# amp_soha.net
KiCad netlist of a schematic drawn in EAGLE
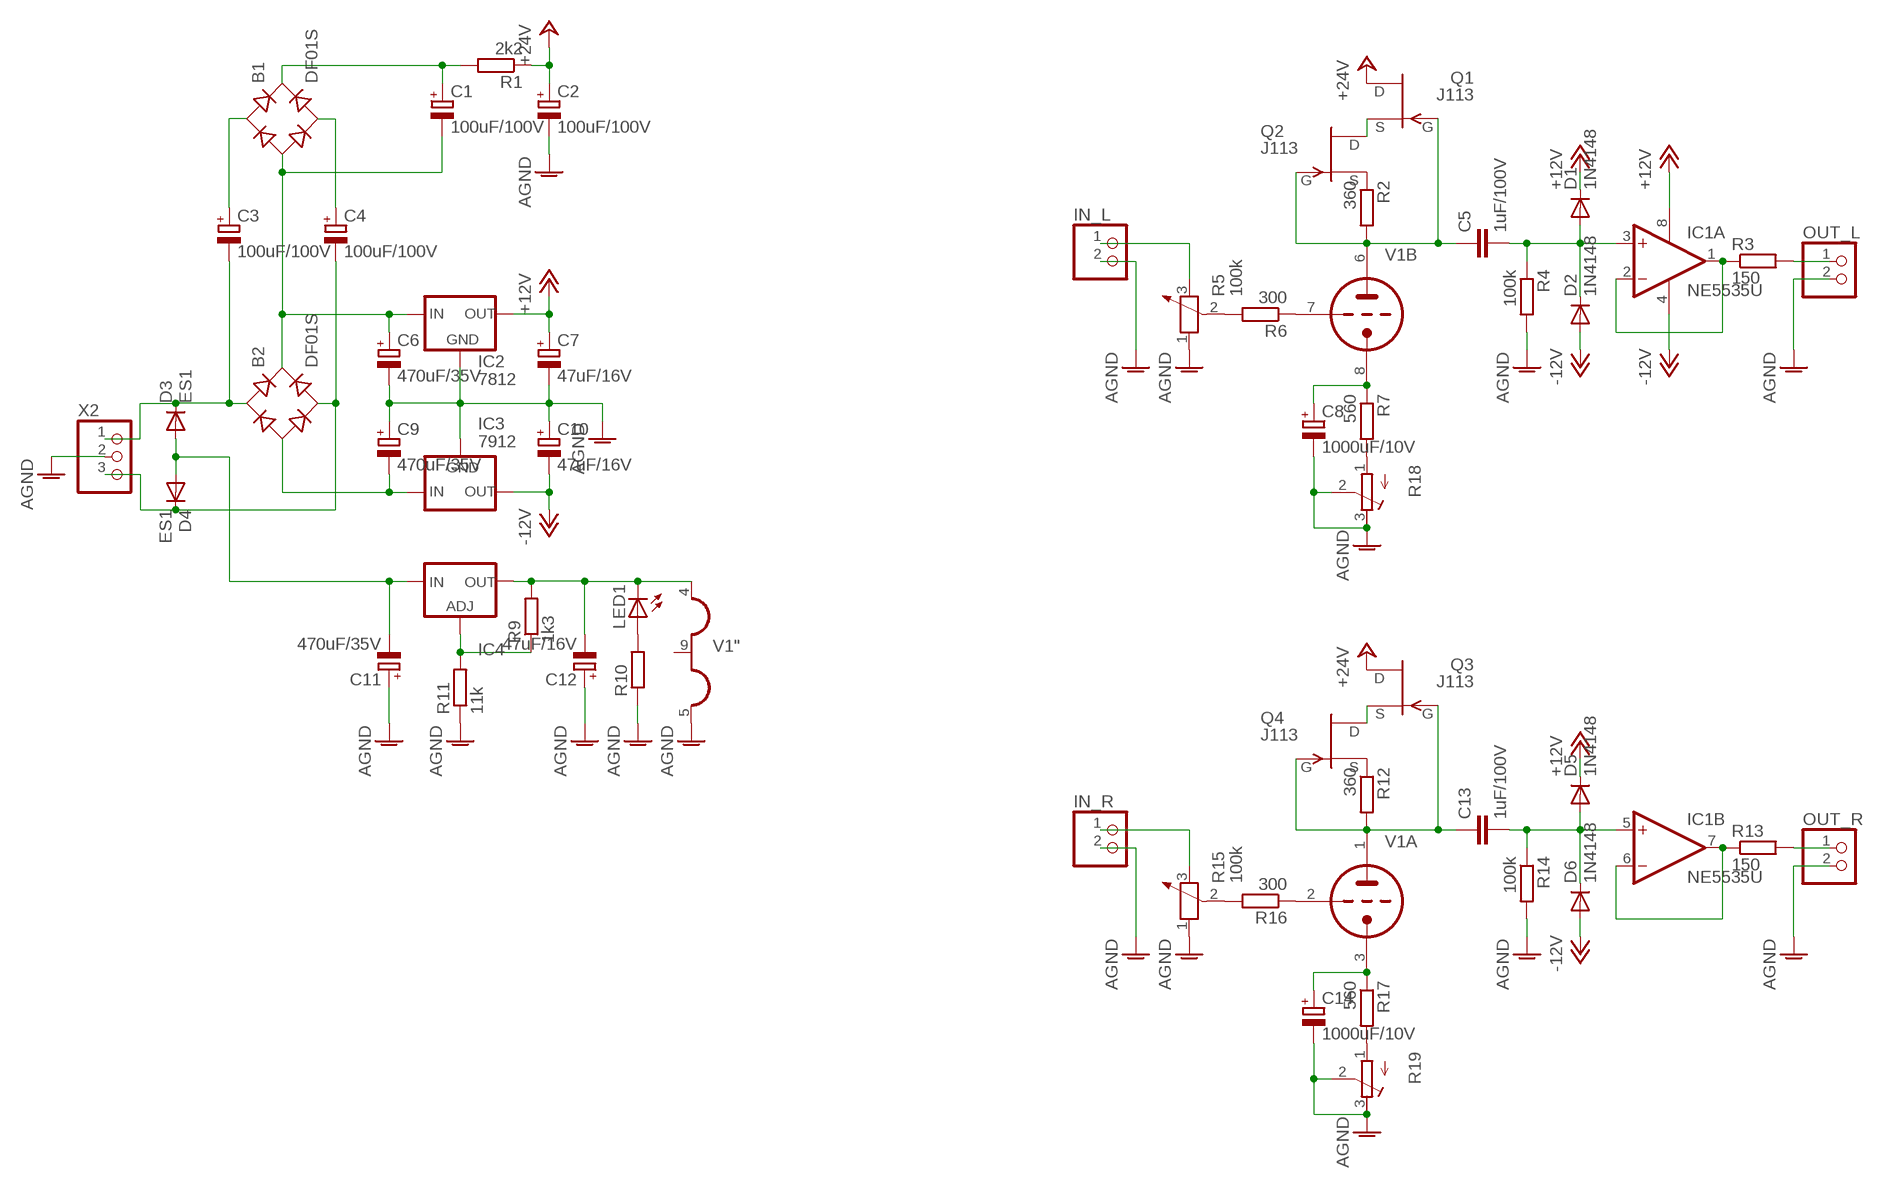
[diagram p0: schematic, sheet 1]

(export (version "E")
  (design (tool "Eeschema 10.0.6"))
  (components
    (comp (ref "B1")
      (value "DF01S")
      (footprint "eagle-import:DFS")
      (libsource (lib "eagle-import") (part "DFS01"))
    )
    (comp (ref "B2")
      (value "DF01S")
      (footprint "eagle-import:DFS")
      (libsource (lib "eagle-import") (part "DFS01"))
    )
    (comp (ref "C1")
      (value "100uF/100V")
      (footprint "eagle-import:E5-10,5")
      (libsource (lib "eagle-import") (part "CPOL-EUE5-10,5"))
    )
    (comp (ref "C2")
      (value "100uF/100V")
      (footprint "eagle-import:E5-10,5")
      (libsource (lib "eagle-import") (part "CPOL-EUE5-10,5"))
    )
    (comp (ref "C3")
      (value "100uF/100V")
      (footprint "eagle-import:E5-10,5")
      (libsource (lib "eagle-import") (part "CPOL-EUE5-10,5"))
    )
    (comp (ref "C4")
      (value "100uF/100V")
      (footprint "eagle-import:E5-10,5")
      (libsource (lib "eagle-import") (part "CPOL-EUE5-10,5"))
    )
    (comp (ref "C5")
      (value "1uF/100V")
      (footprint "eagle-import:C075-052X106")
      (libsource (lib "eagle-import") (part "C-EU075-052X106"))
    )
    (comp (ref "C6")
      (value "470uF/35V")
      (footprint "eagle-import:E5-10,5")
      (libsource (lib "eagle-import") (part "CPOL-EUE5-10,5"))
    )
    (comp (ref "C7")
      (value "47uF/16V")
      (footprint "eagle-import:E2,5-6")
      (libsource (lib "eagle-import") (part "CPOL-EUE2.5-6"))
    )
    (comp (ref "C8")
      (value "1000uF/10V")
      (footprint "eagle-import:E5-10,5")
      (libsource (lib "eagle-import") (part "CPOL-EUE5-10,5"))
    )
    (comp (ref "C9")
      (value "470uF/35V")
      (footprint "eagle-import:E5-10,5")
      (libsource (lib "eagle-import") (part "CPOL-EUE5-10,5"))
    )
    (comp (ref "C10")
      (value "47uF/16V")
      (footprint "eagle-import:E2,5-6")
      (libsource (lib "eagle-import") (part "CPOL-EUE2.5-6"))
    )
    (comp (ref "C11")
      (value "470uF/35V")
      (footprint "eagle-import:E5-10,5")
      (libsource (lib "eagle-import") (part "CPOL-EUE5-10,5"))
    )
    (comp (ref "C12")
      (value "47uF/16V")
      (footprint "eagle-import:E2,5-6")
      (libsource (lib "eagle-import") (part "CPOL-EUE2.5-6"))
    )
    (comp (ref "C13")
      (value "1uF/100V")
      (footprint "eagle-import:C075-052X106")
      (libsource (lib "eagle-import") (part "C-EU075-052X106"))
    )
    (comp (ref "C14")
      (value "1000uF/10V")
      (footprint "eagle-import:E5-10,5")
      (libsource (lib "eagle-import") (part "CPOL-EUE5-10,5"))
    )
    (comp (ref "D1")
      (value "1N4148")
      (footprint "eagle-import:D0805")
      (libsource (lib "eagle-import") (part "1N4148"))
    )
    (comp (ref "D2")
      (value "1N4148")
      (footprint "eagle-import:D0805")
      (libsource (lib "eagle-import") (part "1N4148"))
    )
    (comp (ref "D3")
      (value "ES1")
      (footprint "eagle-import:DO-214AC")
      (libsource (lib "eagle-import") (part "ES1"))
    )
    (comp (ref "D4")
      (value "ES1")
      (footprint "eagle-import:DO-214AC")
      (libsource (lib "eagle-import") (part "ES1"))
    )
    (comp (ref "D5")
      (value "1N4148")
      (footprint "eagle-import:D0805")
      (libsource (lib "eagle-import") (part "1N4148"))
    )
    (comp (ref "D6")
      (value "1N4148")
      (footprint "eagle-import:D0805")
      (libsource (lib "eagle-import") (part "1N4148"))
    )
    (comp (ref "IC1")
      (value "NE5535U")
      (footprint "eagle-import:SO08")
      (libsource (lib "eagle-import") (part "NE5535U"))
    )
    (comp (ref "IC2")
      (value "7812")
      (footprint "eagle-import:78XXS")
      (libsource (lib "eagle-import") (part "78XXTO-220"))
    )
    (comp (ref "IC3")
      (value "7912")
      (footprint "eagle-import:79XXS")
      (libsource (lib "eagle-import") (part "79XXTO-220"))
    )
    (comp (ref "IC4")
      (value "LM337TS")
      (footprint "eagle-import:337TS")
      (libsource (lib "eagle-import") (part "LM337TS"))
    )
    (comp (ref "IN_L")
      (value "PINHD-1X2")
      (footprint "eagle-import:1X02")
      (libsource (lib "eagle-import") (part "PINHD-1X2"))
    )
    (comp (ref "IN_R")
      (value "PINHD-1X2")
      (footprint "eagle-import:1X02")
      (libsource (lib "eagle-import") (part "PINHD-1X2"))
    )
    (comp (ref "LED1")
      (value "LED5MM")
      (footprint "eagle-import:LED5MM")
      (libsource (lib "eagle-import") (part "LED5MM"))
    )
    (comp (ref "OUT_L")
      (value "PINHD-1X2")
      (footprint "eagle-import:1X02")
      (libsource (lib "eagle-import") (part "PINHD-1X2"))
    )
    (comp (ref "OUT_R")
      (value "PINHD-1X2")
      (footprint "eagle-import:1X02")
      (libsource (lib "eagle-import") (part "PINHD-1X2"))
    )
    (comp (ref "Q1")
      (value "J113")
      (footprint "eagle-import:TO92")
      (libsource (lib "eagle-import") (part "J113"))
    )
    (comp (ref "Q2")
      (value "J113")
      (footprint "eagle-import:TO92")
      (libsource (lib "eagle-import") (part "J113"))
    )
    (comp (ref "Q3")
      (value "J113")
      (footprint "eagle-import:TO92")
      (libsource (lib "eagle-import") (part "J113"))
    )
    (comp (ref "Q4")
      (value "J113")
      (footprint "eagle-import:TO92")
      (libsource (lib "eagle-import") (part "J113"))
    )
    (comp (ref "R1")
      (value "2k2")
      (footprint "eagle-import:R0805")
      (libsource (lib "eagle-import") (part "R-EU_"))
    )
    (comp (ref "R2")
      (value "360")
      (footprint "eagle-import:R0805")
      (libsource (lib "eagle-import") (part "R-EU_"))
    )
    (comp (ref "R3")
      (value "150")
      (footprint "eagle-import:R0805")
      (libsource (lib "eagle-import") (part "R-EU_"))
    )
    (comp (ref "R4")
      (value "100k")
      (footprint "eagle-import:R0805")
      (libsource (lib "eagle-import") (part "R-EU_"))
    )
    (comp (ref "R5")
      (value "100k")
      (footprint "eagle-import:1X03")
      (libsource (lib "eagle-import") (part "POTENTIOMETER_"))
    )
    (comp (ref "R6")
      (value "300")
      (footprint "eagle-import:R0805")
      (libsource (lib "eagle-import") (part "R-EU_"))
    )
    (comp (ref "R7")
      (value "560")
      (footprint "eagle-import:R0805")
      (libsource (lib "eagle-import") (part "R-EU_"))
    )
    (comp (ref "R9")
      (value "1k3")
      (footprint "eagle-import:R0805")
      (libsource (lib "eagle-import") (part "R-EU_"))
    )
    (comp (ref "R10")
      (value "R-EU_")
      (footprint "eagle-import:R0805")
      (libsource (lib "eagle-import") (part "R-EU_"))
    )
    (comp (ref "R11")
      (value "11k")
      (footprint "eagle-import:R0805")
      (libsource (lib "eagle-import") (part "R-EU_"))
    )
    (comp (ref "R12")
      (value "360")
      (footprint "eagle-import:R0805")
      (libsource (lib "eagle-import") (part "R-EU_"))
    )
    (comp (ref "R13")
      (value "150")
      (footprint "eagle-import:R0805")
      (libsource (lib "eagle-import") (part "R-EU_"))
    )
    (comp (ref "R14")
      (value "100k")
      (footprint "eagle-import:R0805")
      (libsource (lib "eagle-import") (part "R-EU_"))
    )
    (comp (ref "R15")
      (value "100k")
      (footprint "eagle-import:1X03")
      (libsource (lib "eagle-import") (part "POTENTIOMETER_"))
    )
    (comp (ref "R16")
      (value "300")
      (footprint "eagle-import:R0805")
      (libsource (lib "eagle-import") (part "R-EU_"))
    )
    (comp (ref "R17")
      (value "560")
      (footprint "eagle-import:R0805")
      (libsource (lib "eagle-import") (part "R-EU_"))
    )
    (comp (ref "R18")
      (value "RTRIM329Y")
      (footprint "eagle-import:RTRIM3296Y")
      (libsource (lib "eagle-import") (part "RTRIM329Y"))
    )
    (comp (ref "R19")
      (value "RTRIM329Y")
      (footprint "eagle-import:RTRIM3296Y")
      (libsource (lib "eagle-import") (part "RTRIM329Y"))
    )
    (comp (ref "V1")
      (value "12AU7-P")
      (footprint "eagle-import:NOVAL")
      (libsource (lib "eagle-import") (part "12AU7-P"))
    )
    (comp (ref "X2")
      (value "W237-103")
      (footprint "eagle-import:W237-103")
      (libsource (lib "eagle-import") (part "W237-103"))
    )
  )
  (nets
    (net (code "1") (name "+12V") (class "Default")
      (node (ref "C7") (pin "+") (pinfunction "+_+") (pintype "passive"))
      (node (ref "D1") (pin "K") (pinfunction "C_K") (pintype "passive"))
      (node (ref "D5") (pin "K") (pinfunction "C_K") (pintype "passive"))
      (node (ref "IC1") (pin "8") (pinfunction "V+_8") (pintype "power_in"))
      (node (ref "IC2") (pin "OUT") (pinfunction "OUT_OUT") (pintype "passive"))
    )
    (net (code "2") (name "+24V") (class "Default")
      (node (ref "C2") (pin "+") (pinfunction "+_+") (pintype "passive"))
      (node (ref "Q1") (pin "3") (pinfunction "D_3") (pintype "passive"))
      (node (ref "Q3") (pin "3") (pinfunction "D_3") (pintype "passive"))
      (node (ref "R1") (pin "1") (pinfunction "1_1") (pintype "passive"))
    )
    (net (code "3") (name "-12V") (class "Default")
      (node (ref "C10") (pin "-") (pinfunction "-_-") (pintype "passive"))
      (node (ref "D2") (pin "A") (pinfunction "A_A") (pintype "passive"))
      (node (ref "D6") (pin "A") (pinfunction "A_A") (pintype "passive"))
      (node (ref "IC1") (pin "4") (pinfunction "V-_4") (pintype "power_in"))
      (node (ref "IC3") (pin "OUT") (pinfunction "OUT_OUT") (pintype "passive"))
    )
    (net (code "4") (name "AGND") (class "Default")
      (node (ref "C10") (pin "+") (pinfunction "+_+") (pintype "passive"))
      (node (ref "C11") (pin "+") (pinfunction "+_+") (pintype "passive"))
      (node (ref "C12") (pin "+") (pinfunction "+_+") (pintype "passive"))
      (node (ref "C14") (pin "-") (pinfunction "-_-") (pintype "passive"))
      (node (ref "C2") (pin "-") (pinfunction "-_-") (pintype "passive"))
      (node (ref "C6") (pin "-") (pinfunction "-_-") (pintype "passive"))
      (node (ref "C7") (pin "-") (pinfunction "-_-") (pintype "passive"))
      (node (ref "C8") (pin "-") (pinfunction "-_-") (pintype "passive"))
      (node (ref "C9") (pin "+") (pinfunction "+_+") (pintype "passive"))
      (node (ref "IC2") (pin "GND") (pinfunction "GND_GND") (pintype "input"))
      (node (ref "IC3") (pin "GND") (pinfunction "GND_GND") (pintype "input"))
      (node (ref "IN_L") (pin "2") (pinfunction "2_2") (pintype "passive"))
      (node (ref "IN_R") (pin "2") (pinfunction "2_2") (pintype "passive"))
      (node (ref "OUT_L") (pin "2") (pinfunction "2_2") (pintype "passive"))
      (node (ref "OUT_R") (pin "2") (pinfunction "2_2") (pintype "passive"))
      (node (ref "R10") (pin "1") (pinfunction "1_1") (pintype "passive"))
      (node (ref "R11") (pin "1") (pinfunction "1_1") (pintype "passive"))
      (node (ref "R14") (pin "2") (pinfunction "2_2") (pintype "passive"))
      (node (ref "R15") (pin "1") (pinfunction "1_1") (pintype "passive"))
      (node (ref "R18") (pin "2") (pinfunction "S_2") (pintype "passive"))
      (node (ref "R18") (pin "3") (pinfunction "E_3") (pintype "passive"))
      (node (ref "R19") (pin "2") (pinfunction "S_2") (pintype "passive"))
      (node (ref "R19") (pin "3") (pinfunction "E_3") (pintype "passive"))
      (node (ref "R4") (pin "2") (pinfunction "2_2") (pintype "passive"))
      (node (ref "R5") (pin "1") (pinfunction "1_1") (pintype "passive"))
      (node (ref "V1") (pin "5") (pinfunction "H3_5") (pintype "passive"))
      (node (ref "X2") (pin "2") (pinfunction "2_2") (pintype "passive"))
    )
    (net (code "5") (name "Net-(B1-Pad+)") (class "Default")
      (node (ref "B1") (pin "+") (pinfunction "+_+") (pintype "passive"))
      (node (ref "C1") (pin "+") (pinfunction "+_+") (pintype "passive"))
      (node (ref "R1") (pin "2") (pinfunction "2_2") (pintype "passive"))
    )
    (net (code "6") (name "Net-(B1-Pad-)") (class "Default")
      (node (ref "B1") (pin "-") (pinfunction "-_-") (pintype "passive"))
      (node (ref "B2") (pin "+") (pinfunction "+_+") (pintype "passive"))
      (node (ref "C1") (pin "-") (pinfunction "-_-") (pintype "passive"))
      (node (ref "C6") (pin "+") (pinfunction "+_+") (pintype "passive"))
      (node (ref "IC2") (pin "IN") (pinfunction "IN_IN") (pintype "input"))
    )
    (net (code "7") (name "Net-(B1-PadAC1)") (class "Default")
      (node (ref "B1") (pin "AC1") (pinfunction "AC1_AC1") (pintype "passive"))
      (node (ref "C3") (pin "+") (pinfunction "+_+") (pintype "passive"))
    )
    (net (code "8") (name "Net-(B1-PadAC2)") (class "Default")
      (node (ref "B1") (pin "AC2") (pinfunction "AC2_AC2") (pintype "passive"))
      (node (ref "C4") (pin "+") (pinfunction "+_+") (pintype "passive"))
    )
    (net (code "9") (name "Net-(B2-Pad-)") (class "Default")
      (node (ref "B2") (pin "-") (pinfunction "-_-") (pintype "passive"))
      (node (ref "C9") (pin "-") (pinfunction "-_-") (pintype "passive"))
      (node (ref "IC3") (pin "IN") (pinfunction "IN_IN") (pintype "input"))
    )
    (net (code "10") (name "Net-(B2-PadAC1)") (class "Default")
      (node (ref "B2") (pin "AC1") (pinfunction "AC1_AC1") (pintype "passive"))
      (node (ref "C3") (pin "-") (pinfunction "-_-") (pintype "passive"))
      (node (ref "D3") (pin "C") (pinfunction "C_C") (pintype "passive"))
      (node (ref "X2") (pin "1") (pinfunction "1_1") (pintype "passive"))
    )
    (net (code "11") (name "Net-(B2-PadAC2)") (class "Default")
      (node (ref "B2") (pin "AC2") (pinfunction "AC2_AC2") (pintype "passive"))
      (node (ref "C4") (pin "-") (pinfunction "-_-") (pintype "passive"))
      (node (ref "D4") (pin "C") (pinfunction "C_C") (pintype "passive"))
      (node (ref "X2") (pin "3") (pinfunction "3_3") (pintype "passive"))
    )
    (net (code "12") (name "Net-(D2-C)") (class "Default")
      (node (ref "C5") (pin "2") (pinfunction "2_2") (pintype "passive"))
      (node (ref "D1") (pin "A") (pinfunction "A_A") (pintype "passive"))
      (node (ref "D2") (pin "K") (pinfunction "C_K") (pintype "passive"))
      (node (ref "IC1") (pin "3") (pinfunction "+IN_3") (pintype "input"))
      (node (ref "R4") (pin "1") (pinfunction "1_1") (pintype "passive"))
    )
    (net (code "13") (name "Net-(D6-C)") (class "Default")
      (node (ref "C13") (pin "2") (pinfunction "2_2") (pintype "passive"))
      (node (ref "D5") (pin "A") (pinfunction "A_A") (pintype "passive"))
      (node (ref "D6") (pin "K") (pinfunction "C_K") (pintype "passive"))
      (node (ref "IC1") (pin "5") (pinfunction "+IN_5") (pintype "input"))
      (node (ref "R14") (pin "1") (pinfunction "1_1") (pintype "passive"))
    )
    (net (code "14") (name "Net-(IC1A--IN)") (class "Default")
      (node (ref "IC1") (pin "1") (pinfunction "OUT_1") (pintype "output"))
      (node (ref "IC1") (pin "2") (pinfunction "-IN_2") (pintype "input"))
      (node (ref "R3") (pin "1") (pinfunction "1_1") (pintype "passive"))
    )
    (net (code "15") (name "Net-(IC1B--IN)") (class "Default")
      (node (ref "IC1") (pin "6") (pinfunction "-IN_6") (pintype "input"))
      (node (ref "IC1") (pin "7") (pinfunction "OUT_7") (pintype "output"))
      (node (ref "R13") (pin "1") (pinfunction "1_1") (pintype "passive"))
    )
    (net (code "16") (name "Net-(IC4-ADJ)") (class "Default")
      (node (ref "IC4") (pin "1") (pinfunction "ADJ_1") (pintype "input"))
      (node (ref "R11") (pin "2") (pinfunction "2_2") (pintype "passive"))
      (node (ref "R9") (pin "1") (pinfunction "1_1") (pintype "passive"))
    )
    (net (code "17") (name "Net-(IC4-IN)") (class "Default")
      (node (ref "C11") (pin "-") (pinfunction "-_-") (pintype "passive"))
      (node (ref "D3") (pin "A") (pinfunction "A_A") (pintype "passive"))
      (node (ref "D4") (pin "A") (pinfunction "A_A") (pintype "passive"))
      (node (ref "IC4") (pin "2") (pinfunction "IN_2") (pintype "input"))
    )
    (net (code "18") (name "Net-(IC4-OUT)") (class "Default")
      (node (ref "C12") (pin "-") (pinfunction "-_-") (pintype "passive"))
      (node (ref "IC4") (pin "3") (pinfunction "OUT_3") (pintype "passive"))
      (node (ref "LED1") (pin "K") (pinfunction "C_K") (pintype "passive"))
      (node (ref "R9") (pin "2") (pinfunction "2_2") (pintype "passive"))
      (node (ref "V1") (pin "4") (pinfunction "H1_4") (pintype "passive"))
    )
    (net (code "19") (name "Net-(LED1-PadA)") (class "Default")
      (node (ref "LED1") (pin "A") (pinfunction "A_A") (pintype "passive"))
      (node (ref "R10") (pin "2") (pinfunction "2_2") (pintype "passive"))
    )
    (net (code "20") (name "Net-(OUT_L-Pad1)") (class "Default")
      (node (ref "OUT_L") (pin "1") (pinfunction "1_1") (pintype "passive"))
      (node (ref "R3") (pin "2") (pinfunction "2_2") (pintype "passive"))
    )
    (net (code "21") (name "Net-(OUT_R-Pad1)") (class "Default")
      (node (ref "OUT_R") (pin "1") (pinfunction "1_1") (pintype "passive"))
      (node (ref "R13") (pin "2") (pinfunction "2_2") (pintype "passive"))
    )
    (net (code "22") (name "Net-(Q1-G)") (class "Default")
      (node (ref "C5") (pin "1") (pinfunction "1_1") (pintype "passive"))
      (node (ref "Q1") (pin "1") (pinfunction "G_1") (pintype "passive"))
      (node (ref "Q2") (pin "1") (pinfunction "G_1") (pintype "passive"))
      (node (ref "R2") (pin "2") (pinfunction "2_2") (pintype "passive"))
      (node (ref "V1") (pin "6") (pinfunction "TA_6") (pintype "passive"))
    )
    (net (code "23") (name "Net-(Q1-S)") (class "Default")
      (node (ref "Q1") (pin "2") (pinfunction "S_2") (pintype "passive"))
      (node (ref "Q2") (pin "3") (pinfunction "D_3") (pintype "passive"))
    )
    (net (code "24") (name "Net-(Q2-S)") (class "Default")
      (node (ref "Q2") (pin "2") (pinfunction "S_2") (pintype "passive"))
      (node (ref "R2") (pin "1") (pinfunction "1_1") (pintype "passive"))
    )
    (net (code "25") (name "Net-(Q3-G)") (class "Default")
      (node (ref "C13") (pin "1") (pinfunction "1_1") (pintype "passive"))
      (node (ref "Q3") (pin "1") (pinfunction "G_1") (pintype "passive"))
      (node (ref "Q4") (pin "1") (pinfunction "G_1") (pintype "passive"))
      (node (ref "R12") (pin "2") (pinfunction "2_2") (pintype "passive"))
      (node (ref "V1") (pin "1") (pinfunction "TA_1") (pintype "passive"))
    )
    (net (code "26") (name "Net-(Q3-S)") (class "Default")
      (node (ref "Q3") (pin "2") (pinfunction "S_2") (pintype "passive"))
      (node (ref "Q4") (pin "3") (pinfunction "D_3") (pintype "passive"))
    )
    (net (code "27") (name "Net-(Q4-S)") (class "Default")
      (node (ref "Q4") (pin "2") (pinfunction "S_2") (pintype "passive"))
      (node (ref "R12") (pin "1") (pinfunction "1_1") (pintype "passive"))
    )
    (net (code "28") (name "Net-(R5-2)") (class "Default")
      (node (ref "IN_L") (pin "1") (pinfunction "1_1") (pintype "passive"))
      (node (ref "R5") (pin "3") (pinfunction "2_3") (pintype "passive"))
    )
    (net (code "29") (name "Net-(R5-3)") (class "Default")
      (node (ref "R5") (pin "2") (pinfunction "3_2") (pintype "passive"))
      (node (ref "R6") (pin "2") (pinfunction "2_2") (pintype "passive"))
    )
    (net (code "30") (name "Net-(R15-2)") (class "Default")
      (node (ref "IN_R") (pin "1") (pinfunction "1_1") (pintype "passive"))
      (node (ref "R15") (pin "3") (pinfunction "2_3") (pintype "passive"))
    )
    (net (code "31") (name "Net-(R15-3)") (class "Default")
      (node (ref "R15") (pin "2") (pinfunction "3_2") (pintype "passive"))
      (node (ref "R16") (pin "2") (pinfunction "2_2") (pintype "passive"))
    )
    (net (code "32") (name "Net-(R18-A)") (class "Default")
      (node (ref "R18") (pin "1") (pinfunction "A_1") (pintype "passive"))
      (node (ref "R7") (pin "2") (pinfunction "2_2") (pintype "passive"))
    )
    (net (code "33") (name "Net-(R19-A)") (class "Default")
      (node (ref "R17") (pin "2") (pinfunction "2_2") (pintype "passive"))
      (node (ref "R19") (pin "1") (pinfunction "A_1") (pintype "passive"))
    )
    (net (code "34") (name "Net-(V1B-TG)") (class "Default")
      (node (ref "R16") (pin "1") (pinfunction "1_1") (pintype "passive"))
      (node (ref "V1") (pin "2") (pinfunction "TG_2") (pintype "passive"))
    )
    (net (code "35") (name "Net-(V1B-TK)") (class "Default")
      (node (ref "C14") (pin "+") (pinfunction "+_+") (pintype "passive"))
      (node (ref "R17") (pin "1") (pinfunction "1_1") (pintype "passive"))
      (node (ref "V1") (pin "3") (pinfunction "TK_3") (pintype "passive"))
    )
    (net (code "36") (name "Net-(V1C-TG)") (class "Default")
      (node (ref "R6") (pin "1") (pinfunction "1_1") (pintype "passive"))
      (node (ref "V1") (pin "7") (pinfunction "TG_7") (pintype "passive"))
    )
    (net (code "37") (name "Net-(V1C-TK)") (class "Default")
      (node (ref "C8") (pin "+") (pinfunction "+_+") (pintype "passive"))
      (node (ref "R7") (pin "1") (pinfunction "1_1") (pintype "passive"))
      (node (ref "V1") (pin "8") (pinfunction "TK_8") (pintype "passive"))
    )
    (net (code "38") (name "unconnected-(V1A-H2-Pad9)") (class "Default")
      (node (ref "V1") (pin "9") (pinfunction "H2_9") (pintype "passive"))
    )
  )
)
